# Sheet3.net
KiCad netlist of a schematic drawn in Altium Designer
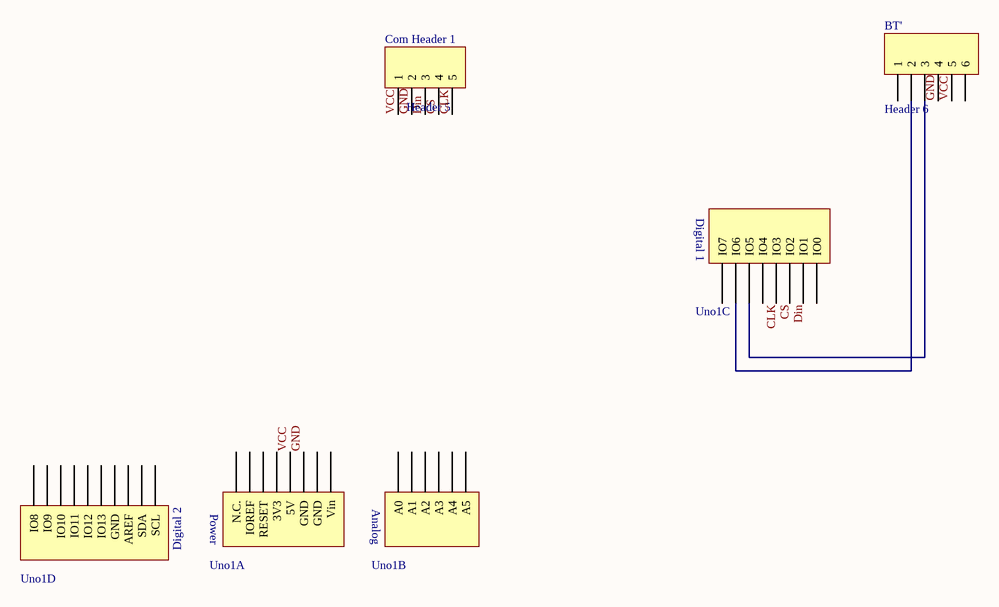
[diagram p0: Sheet3.SchDoc]

(export (version "E")
  (design (tool "Eeschema 10.0.6"))
  (components
    (comp (ref "BT'")
      (value "Header 6")
      (footprint "HDR1X6")
      (description "Header, 6-Pin")
      (fields (field (name "PUBLISHER") "Altium Limited"))
      (libsource (lib "Miscellaneous Connectors") (part "Header 6"))
    )
    (comp (ref "Com Header 1")
      (value "Header 5")
      (footprint "HDR1X5")
      (description "Header, 5-Pin")
      (fields (field (name "PUBLISHER") "Altium Limited"))
      (libsource (lib "Miscellaneous Connectors") (part "Header 5"))
    )
    (comp (ref "Uno1")
      (value "Arduino Uno")
      (footprint "Arduino Uno")
      (libsource (lib "Arduino") (part "Arduino Uno"))
    )
  )
  (nets
    (net (code "1") (name "/CLK") (class "Default")
      (node (ref "Com Header 1") (pin "5") (pinfunction "5_5") (pintype "passive"))
      (node (ref "Uno1") (pin "4") (pinfunction "IO4_4") (pintype "passive"))
    )
    (net (code "2") (name "/CS") (class "Default")
      (node (ref "Com Header 1") (pin "4") (pinfunction "4_4") (pintype "passive"))
      (node (ref "Uno1") (pin "3") (pinfunction "IO3_3") (pintype "passive"))
    )
    (net (code "3") (name "/Din") (class "Default")
      (node (ref "Com Header 1") (pin "3") (pinfunction "3_3") (pintype "passive"))
      (node (ref "Uno1") (pin "2") (pinfunction "IO2_2") (pintype "passive"))
    )
    (net (code "4") (name "/GND") (class "Default")
      (node (ref "BT'") (pin "4") (pinfunction "4_4") (pintype "passive"))
      (node (ref "Com Header 1") (pin "2") (pinfunction "2_2") (pintype "passive"))
      (node (ref "Uno1") (pin "GND1") (pinfunction "GND_GND1") (pintype "passive"))
    )
    (net (code "5") (name "/VCC") (class "Default")
      (node (ref "BT'") (pin "5") (pinfunction "5_5") (pintype "passive"))
      (node (ref "Com Header 1") (pin "1") (pinfunction "1_1") (pintype "passive"))
      (node (ref "Uno1") (pin "5V") (pinfunction "5V_5V") (pintype "passive"))
    )
    (net (code "6") (name "Net-(Uno1C-IO5)") (class "Default")
      (node (ref "BT'") (pin "3") (pinfunction "3_3") (pintype "passive"))
      (node (ref "Uno1") (pin "5") (pinfunction "IO5_5") (pintype "passive"))
    )
    (net (code "7") (name "Net-(Uno1C-IO6)") (class "Default")
      (node (ref "BT'") (pin "2") (pinfunction "2_2") (pintype "passive"))
      (node (ref "Uno1") (pin "6") (pinfunction "IO6_6") (pintype "passive"))
    )
    (net (code "8") (name "unconnected-(BT'-Pad1)") (class "Default")
      (node (ref "BT'") (pin "1") (pinfunction "1_1") (pintype "passive"))
    )
    (net (code "9") (name "unconnected-(BT'-Pad6)") (class "Default")
      (node (ref "BT'") (pin "6") (pinfunction "6_6") (pintype "passive"))
    )
    (net (code "10") (name "unconnected-(Uno1-Pad3V3)") (class "Default")
      (node (ref "Uno1") (pin "3V3") (pinfunction "3V3_3V3") (pintype "passive"))
    )
    (net (code "11") (name "unconnected-(Uno1-PadA0)") (class "Default")
      (node (ref "Uno1") (pin "A0") (pinfunction "A0_A0") (pintype "passive"))
    )
    (net (code "12") (name "unconnected-(Uno1-PadA1)") (class "Default")
      (node (ref "Uno1") (pin "A1") (pinfunction "A1_A1") (pintype "passive"))
    )
    (net (code "13") (name "unconnected-(Uno1-PadA2)") (class "Default")
      (node (ref "Uno1") (pin "A2") (pinfunction "A2_A2") (pintype "passive"))
    )
    (net (code "14") (name "unconnected-(Uno1-PadA3)") (class "Default")
      (node (ref "Uno1") (pin "A3") (pinfunction "A3_A3") (pintype "passive"))
    )
    (net (code "15") (name "unconnected-(Uno1-PadA4)") (class "Default")
      (node (ref "Uno1") (pin "A4") (pinfunction "A4_A4") (pintype "passive"))
    )
    (net (code "16") (name "unconnected-(Uno1-PadA5)") (class "Default")
      (node (ref "Uno1") (pin "A5") (pinfunction "A5_A5") (pintype "passive"))
    )
    (net (code "17") (name "unconnected-(Uno1-PadAREF)") (class "Default")
      (node (ref "Uno1") (pin "AREF") (pinfunction "AREF_AREF") (pintype "passive"))
    )
    (net (code "18") (name "unconnected-(Uno1-PadIOREF)") (class "Default")
      (node (ref "Uno1") (pin "IOREF") (pinfunction "IOREF_IOREF") (pintype "passive"))
    )
    (net (code "19") (name "unconnected-(Uno1-PadRESET)") (class "Default")
      (node (ref "Uno1") (pin "RESET") (pinfunction "RESET_RESET") (pintype "passive"))
    )
    (net (code "20") (name "unconnected-(Uno1-PadSCL)") (class "Default")
      (node (ref "Uno1") (pin "SCL") (pinfunction "SCL_SCL") (pintype "passive"))
    )
    (net (code "21") (name "unconnected-(Uno1-PadSDA)") (class "Default")
      (node (ref "Uno1") (pin "SDA") (pinfunction "SDA_SDA") (pintype "passive"))
    )
    (net (code "22") (name "unconnected-(Uno1-PadVin)") (class "Default")
      (node (ref "Uno1") (pin "Vin") (pinfunction "Vin_Vin") (pintype "passive"))
    )
    (net (code "23") (name "unconnected-(Uno1A-GND-PadGND2)") (class "Default")
      (node (ref "Uno1") (pin "GND2") (pinfunction "GND_GND2") (pintype "passive"))
    )
    (net (code "24") (name "unconnected-(Uno1A-N.C.-PadNC)") (class "Default")
      (node (ref "Uno1") (pin "NC") (pinfunction "N.C._NC") (pintype "passive"))
    )
    (net (code "25") (name "unconnected-(Uno1C-IO0-Pad0)") (class "Default")
      (node (ref "Uno1") (pin "0") (pinfunction "IO0_0") (pintype "passive"))
    )
    (net (code "26") (name "unconnected-(Uno1C-IO1-Pad1)") (class "Default")
      (node (ref "Uno1") (pin "1") (pinfunction "IO1_1") (pintype "passive"))
    )
    (net (code "27") (name "unconnected-(Uno1C-IO7-Pad7)") (class "Default")
      (node (ref "Uno1") (pin "7") (pinfunction "IO7_7") (pintype "passive"))
    )
    (net (code "28") (name "unconnected-(Uno1D-GND-PadGND3)") (class "Default")
      (node (ref "Uno1") (pin "GND3") (pinfunction "GND_GND3") (pintype "passive"))
    )
    (net (code "29") (name "unconnected-(Uno1D-IO8-Pad8)") (class "Default")
      (node (ref "Uno1") (pin "8") (pinfunction "IO8_8") (pintype "passive"))
    )
    (net (code "30") (name "unconnected-(Uno1D-IO9-Pad9)") (class "Default")
      (node (ref "Uno1") (pin "9") (pinfunction "IO9_9") (pintype "passive"))
    )
    (net (code "31") (name "unconnected-(Uno1D-IO10-Pad10)") (class "Default")
      (node (ref "Uno1") (pin "10") (pinfunction "IO10_10") (pintype "passive"))
    )
    (net (code "32") (name "unconnected-(Uno1D-IO11-Pad11)") (class "Default")
      (node (ref "Uno1") (pin "11") (pinfunction "IO11_11") (pintype "passive"))
    )
    (net (code "33") (name "unconnected-(Uno1D-IO12-Pad12)") (class "Default")
      (node (ref "Uno1") (pin "12") (pinfunction "IO12_12") (pintype "passive"))
    )
    (net (code "34") (name "unconnected-(Uno1D-IO13-Pad13)") (class "Default")
      (node (ref "Uno1") (pin "13") (pinfunction "IO13_13") (pintype "passive"))
    )
  )
)
